# 11-DPLL-2.net
KiCad netlist of a schematic drawn in Altium Designer
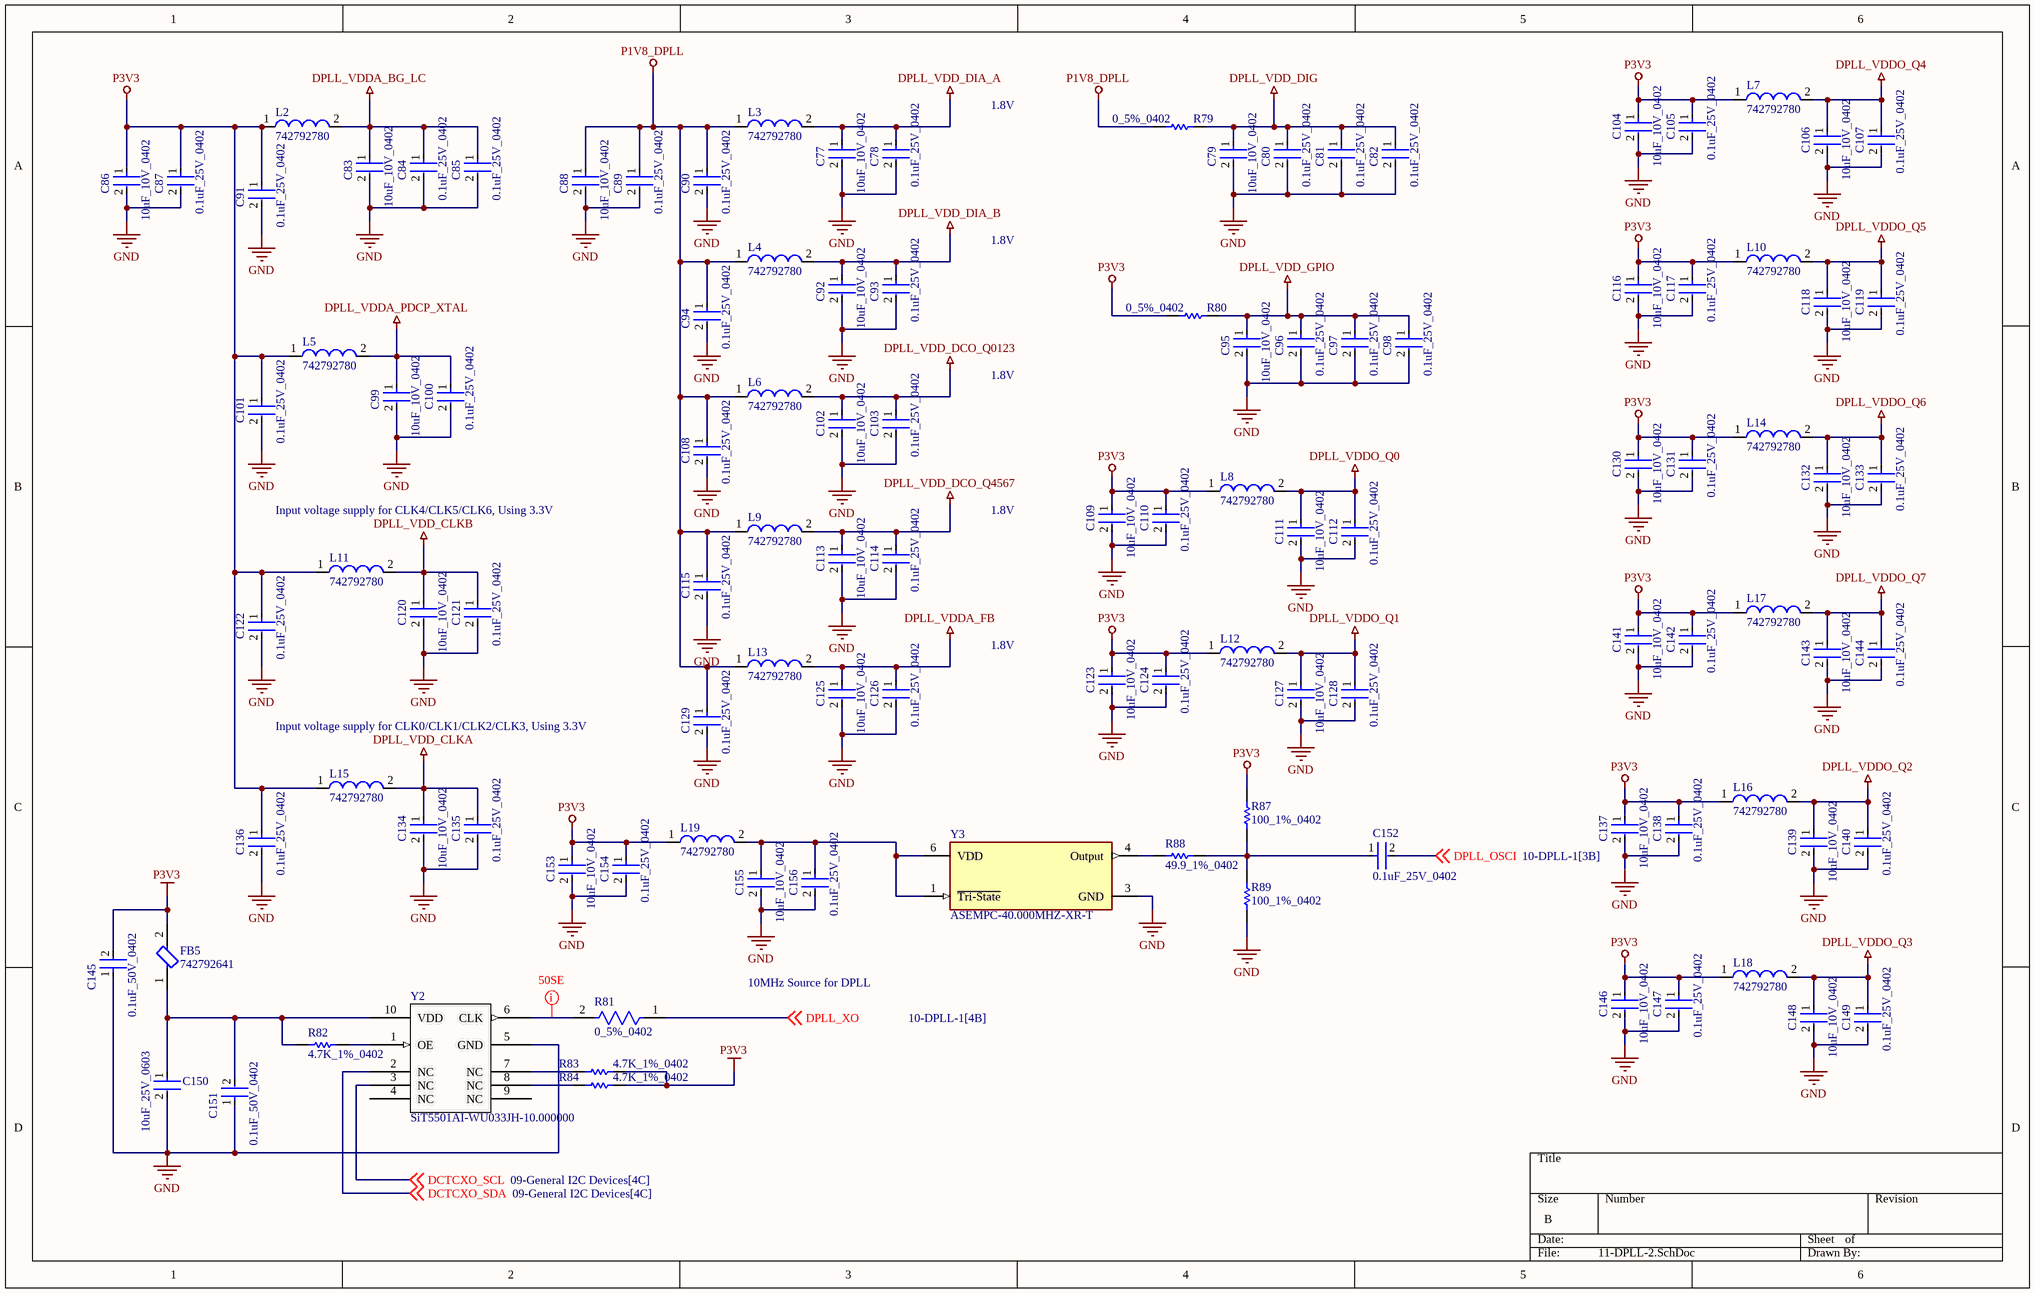
[diagram p0: 11-DPLL-2.SchDoc]

(export (version "E")
  (design (tool "Eeschema 10.0.6"))
  (components
    (comp (ref "C77")
      (value "10uF_10V_0402")
      (footprint "FP-CL05A106MP5NUNC-MFG")
      (description "CAP CER 10UF 10V X5R 0402")
      (fields
        (field (name "OCTOPART") "https://octopart.com/cl05a106mp5nunc-samsung-22457395")
        (field (name "TOLERANCE") "20%")
      )
      (libsource (lib "Altium Content Vault") (part "b4654b650e69147ec39a6b967a45e02"))
    )
    (comp (ref "C78")
      (value "0.1uF_25V_0402")
      (footprint "FP-0402-L_1_0_1-W_0_5_0_1-IPC_C")
      (description "General Purpose Ceramic Capacitor, 0402, 100nF, 10%, X7R, 15%, 25V")
      (fields (field (name "VOLTAGE") "25V") (field (name "TOLERANCE") "10%"))
      (libsource (lib "Altium Content Vault") (part "b4654b650e69147ec39a6b967a45e02"))
    )
    (comp (ref "C79")
      (value "10uF_10V_0402")
      (footprint "FP-CL05A106MP5NUNC-MFG")
      (description "CAP CER 10UF 10V X5R 0402")
      (fields
        (field (name "OCTOPART") "https://octopart.com/cl05a106mp5nunc-samsung-22457395")
        (field (name "TOLERANCE") "20%")
      )
      (libsource (lib "Altium Content Vault") (part "b4654b650e69147ec39a6b967a45e02"))
    )
    (comp (ref "C80")
      (value "0.1uF_25V_0402")
      (footprint "FP-0402-L_1_0_1-W_0_5_0_1-IPC_C")
      (description "General Purpose Ceramic Capacitor, 0402, 100nF, 10%, X7R, 15%, 25V")
      (fields (field (name "VOLTAGE") "25V") (field (name "TOLERANCE") "10%"))
      (libsource (lib "Altium Content Vault") (part "b4654b650e69147ec39a6b967a45e02"))
    )
    (comp (ref "C81")
      (value "0.1uF_25V_0402")
      (footprint "FP-0402-L_1_0_1-W_0_5_0_1-IPC_C")
      (description "General Purpose Ceramic Capacitor, 0402, 100nF, 10%, X7R, 15%, 25V")
      (fields (field (name "VOLTAGE") "25V") (field (name "TOLERANCE") "10%"))
      (libsource (lib "Altium Content Vault") (part "b4654b650e69147ec39a6b967a45e02"))
    )
    (comp (ref "C82")
      (value "0.1uF_25V_0402")
      (footprint "FP-0402-L_1_0_1-W_0_5_0_1-IPC_C")
      (description "General Purpose Ceramic Capacitor, 0402, 100nF, 10%, X7R, 15%, 25V")
      (fields (field (name "VOLTAGE") "25V") (field (name "TOLERANCE") "10%"))
      (libsource (lib "Altium Content Vault") (part "b4654b650e69147ec39a6b967a45e02"))
    )
    (comp (ref "C83")
      (value "10uF_10V_0402")
      (footprint "FP-CL05A106MP5NUNC-MFG")
      (description "CAP CER 10UF 10V X5R 0402")
      (fields
        (field (name "OCTOPART") "https://octopart.com/cl05a106mp5nunc-samsung-22457395")
        (field (name "TOLERANCE") "20%")
      )
      (libsource (lib "Altium Content Vault") (part "b4654b650e69147ec39a6b967a45e02"))
    )
    (comp (ref "C84")
      (value "0.1uF_25V_0402")
      (footprint "FP-0402-L_1_0_1-W_0_5_0_1-IPC_C")
      (description "General Purpose Ceramic Capacitor, 0402, 100nF, 10%, X7R, 15%, 25V")
      (fields (field (name "VOLTAGE") "25V") (field (name "TOLERANCE") "10%"))
      (libsource (lib "Altium Content Vault") (part "b4654b650e69147ec39a6b967a45e02"))
    )
    (comp (ref "C85")
      (value "0.1uF_25V_0402")
      (footprint "FP-0402-L_1_0_1-W_0_5_0_1-IPC_C")
      (description "General Purpose Ceramic Capacitor, 0402, 100nF, 10%, X7R, 15%, 25V")
      (fields (field (name "VOLTAGE") "25V") (field (name "TOLERANCE") "10%"))
      (libsource (lib "Altium Content Vault") (part "b4654b650e69147ec39a6b967a45e02"))
    )
    (comp (ref "C86")
      (value "10uF_10V_0402")
      (footprint "FP-CL05A106MP5NUNC-MFG")
      (description "CAP CER 10UF 10V X5R 0402")
      (fields
        (field (name "OCTOPART") "https://octopart.com/cl05a106mp5nunc-samsung-22457395")
        (field (name "TOLERANCE") "20%")
      )
      (libsource (lib "Altium Content Vault") (part "b4654b650e69147ec39a6b967a45e02"))
    )
    (comp (ref "C87")
      (value "0.1uF_25V_0402")
      (footprint "FP-0402-L_1_0_1-W_0_5_0_1-IPC_C")
      (description "General Purpose Ceramic Capacitor, 0402, 100nF, 10%, X7R, 15%, 25V")
      (fields (field (name "VOLTAGE") "25V") (field (name "TOLERANCE") "10%"))
      (libsource (lib "Altium Content Vault") (part "b4654b650e69147ec39a6b967a45e02"))
    )
    (comp (ref "C88")
      (value "10uF_10V_0402")
      (footprint "FP-CL05A106MP5NUNC-MFG")
      (description "CAP CER 10UF 10V X5R 0402")
      (fields
        (field (name "OCTOPART") "https://octopart.com/cl05a106mp5nunc-samsung-22457395")
        (field (name "TOLERANCE") "20%")
      )
      (libsource (lib "Altium Content Vault") (part "b4654b650e69147ec39a6b967a45e02"))
    )
    (comp (ref "C89")
      (value "0.1uF_25V_0402")
      (footprint "FP-0402-L_1_0_1-W_0_5_0_1-IPC_C")
      (description "General Purpose Ceramic Capacitor, 0402, 100nF, 10%, X7R, 15%, 25V")
      (fields (field (name "VOLTAGE") "25V") (field (name "TOLERANCE") "10%"))
      (libsource (lib "Altium Content Vault") (part "b4654b650e69147ec39a6b967a45e02"))
    )
    (comp (ref "C90")
      (value "0.1uF_25V_0402")
      (footprint "FP-0402-L_1_0_1-W_0_5_0_1-IPC_C")
      (description "General Purpose Ceramic Capacitor, 0402, 100nF, 10%, X7R, 15%, 25V")
      (fields (field (name "VOLTAGE") "25V") (field (name "TOLERANCE") "10%"))
      (libsource (lib "Altium Content Vault") (part "b4654b650e69147ec39a6b967a45e02"))
    )
    (comp (ref "C91")
      (value "0.1uF_25V_0402")
      (footprint "FP-0402-L_1_0_1-W_0_5_0_1-IPC_C")
      (description "General Purpose Ceramic Capacitor, 0402, 100nF, 10%, X7R, 15%, 25V")
      (fields (field (name "VOLTAGE") "25V") (field (name "TOLERANCE") "10%"))
      (libsource (lib "Altium Content Vault") (part "b4654b650e69147ec39a6b967a45e02"))
    )
    (comp (ref "C92")
      (value "10uF_10V_0402")
      (footprint "FP-CL05A106MP5NUNC-MFG")
      (description "CAP CER 10UF 10V X5R 0402")
      (fields
        (field (name "OCTOPART") "https://octopart.com/cl05a106mp5nunc-samsung-22457395")
        (field (name "TOLERANCE") "20%")
      )
      (libsource (lib "Altium Content Vault") (part "b4654b650e69147ec39a6b967a45e02"))
    )
    (comp (ref "C93")
      (value "0.1uF_25V_0402")
      (footprint "FP-0402-L_1_0_1-W_0_5_0_1-IPC_C")
      (description "General Purpose Ceramic Capacitor, 0402, 100nF, 10%, X7R, 15%, 25V")
      (fields (field (name "VOLTAGE") "25V") (field (name "TOLERANCE") "10%"))
      (libsource (lib "Altium Content Vault") (part "b4654b650e69147ec39a6b967a45e02"))
    )
    (comp (ref "C94")
      (value "0.1uF_25V_0402")
      (footprint "FP-0402-L_1_0_1-W_0_5_0_1-IPC_C")
      (description "General Purpose Ceramic Capacitor, 0402, 100nF, 10%, X7R, 15%, 25V")
      (fields (field (name "VOLTAGE") "25V") (field (name "TOLERANCE") "10%"))
      (libsource (lib "Altium Content Vault") (part "b4654b650e69147ec39a6b967a45e02"))
    )
    (comp (ref "C95")
      (value "10uF_10V_0402")
      (footprint "FP-CL05A106MP5NUNC-MFG")
      (description "CAP CER 10UF 10V X5R 0402")
      (fields
        (field (name "OCTOPART") "https://octopart.com/cl05a106mp5nunc-samsung-22457395")
        (field (name "TOLERANCE") "20%")
      )
      (libsource (lib "Altium Content Vault") (part "b4654b650e69147ec39a6b967a45e02"))
    )
    (comp (ref "C96")
      (value "0.1uF_25V_0402")
      (footprint "FP-0402-L_1_0_1-W_0_5_0_1-IPC_C")
      (description "General Purpose Ceramic Capacitor, 0402, 100nF, 10%, X7R, 15%, 25V")
      (fields (field (name "VOLTAGE") "25V") (field (name "TOLERANCE") "10%"))
      (libsource (lib "Altium Content Vault") (part "b4654b650e69147ec39a6b967a45e02"))
    )
    (comp (ref "C97")
      (value "0.1uF_25V_0402")
      (footprint "FP-0402-L_1_0_1-W_0_5_0_1-IPC_C")
      (description "General Purpose Ceramic Capacitor, 0402, 100nF, 10%, X7R, 15%, 25V")
      (fields (field (name "VOLTAGE") "25V") (field (name "TOLERANCE") "10%"))
      (libsource (lib "Altium Content Vault") (part "b4654b650e69147ec39a6b967a45e02"))
    )
    (comp (ref "C98")
      (value "0.1uF_25V_0402")
      (footprint "FP-0402-L_1_0_1-W_0_5_0_1-IPC_C")
      (description "General Purpose Ceramic Capacitor, 0402, 100nF, 10%, X7R, 15%, 25V")
      (fields (field (name "VOLTAGE") "25V") (field (name "TOLERANCE") "10%"))
      (libsource (lib "Altium Content Vault") (part "b4654b650e69147ec39a6b967a45e02"))
    )
    (comp (ref "C99")
      (value "10uF_10V_0402")
      (footprint "FP-CL05A106MP5NUNC-MFG")
      (description "CAP CER 10UF 10V X5R 0402")
      (fields
        (field (name "OCTOPART") "https://octopart.com/cl05a106mp5nunc-samsung-22457395")
        (field (name "TOLERANCE") "20%")
      )
      (libsource (lib "Altium Content Vault") (part "b4654b650e69147ec39a6b967a45e02"))
    )
    (comp (ref "C100")
      (value "0.1uF_25V_0402")
      (footprint "FP-0402-L_1_0_1-W_0_5_0_1-IPC_C")
      (description "General Purpose Ceramic Capacitor, 0402, 100nF, 10%, X7R, 15%, 25V")
      (fields (field (name "VOLTAGE") "25V") (field (name "TOLERANCE") "10%"))
      (libsource (lib "Altium Content Vault") (part "b4654b650e69147ec39a6b967a45e02"))
    )
    (comp (ref "C101")
      (value "0.1uF_25V_0402")
      (footprint "FP-0402-L_1_0_1-W_0_5_0_1-IPC_C")
      (description "General Purpose Ceramic Capacitor, 0402, 100nF, 10%, X7R, 15%, 25V")
      (fields (field (name "VOLTAGE") "25V") (field (name "TOLERANCE") "10%"))
      (libsource (lib "Altium Content Vault") (part "b4654b650e69147ec39a6b967a45e02"))
    )
    (comp (ref "C102")
      (value "10uF_10V_0402")
      (footprint "FP-CL05A106MP5NUNC-MFG")
      (description "CAP CER 10UF 10V X5R 0402")
      (fields
        (field (name "OCTOPART") "https://octopart.com/cl05a106mp5nunc-samsung-22457395")
        (field (name "TOLERANCE") "20%")
      )
      (libsource (lib "Altium Content Vault") (part "b4654b650e69147ec39a6b967a45e02"))
    )
    (comp (ref "C103")
      (value "0.1uF_25V_0402")
      (footprint "FP-0402-L_1_0_1-W_0_5_0_1-IPC_C")
      (description "General Purpose Ceramic Capacitor, 0402, 100nF, 10%, X7R, 15%, 25V")
      (fields (field (name "VOLTAGE") "25V") (field (name "TOLERANCE") "10%"))
      (libsource (lib "Altium Content Vault") (part "b4654b650e69147ec39a6b967a45e02"))
    )
    (comp (ref "C104")
      (value "10uF_10V_0402")
      (footprint "FP-CL05A106MP5NUNC-MFG")
      (description "CAP CER 10UF 10V X5R 0402")
      (fields
        (field (name "OCTOPART") "https://octopart.com/cl05a106mp5nunc-samsung-22457395")
        (field (name "TOLERANCE") "20%")
      )
      (libsource (lib "Altium Content Vault") (part "b4654b650e69147ec39a6b967a45e02"))
    )
    (comp (ref "C105")
      (value "0.1uF_25V_0402")
      (footprint "FP-0402-L_1_0_1-W_0_5_0_1-IPC_C")
      (description "General Purpose Ceramic Capacitor, 0402, 100nF, 10%, X7R, 15%, 25V")
      (fields (field (name "VOLTAGE") "25V") (field (name "TOLERANCE") "10%"))
      (libsource (lib "Altium Content Vault") (part "b4654b650e69147ec39a6b967a45e02"))
    )
    (comp (ref "C106")
      (value "10uF_10V_0402")
      (footprint "FP-CL05A106MP5NUNC-MFG")
      (description "CAP CER 10UF 10V X5R 0402")
      (fields
        (field (name "OCTOPART") "https://octopart.com/cl05a106mp5nunc-samsung-22457395")
        (field (name "TOLERANCE") "20%")
      )
      (libsource (lib "Altium Content Vault") (part "b4654b650e69147ec39a6b967a45e02"))
    )
    (comp (ref "C107")
      (value "0.1uF_25V_0402")
      (footprint "FP-0402-L_1_0_1-W_0_5_0_1-IPC_C")
      (description "General Purpose Ceramic Capacitor, 0402, 100nF, 10%, X7R, 15%, 25V")
      (fields (field (name "VOLTAGE") "25V") (field (name "TOLERANCE") "10%"))
      (libsource (lib "Altium Content Vault") (part "b4654b650e69147ec39a6b967a45e02"))
    )
    (comp (ref "C108")
      (value "0.1uF_25V_0402")
      (footprint "FP-0402-L_1_0_1-W_0_5_0_1-IPC_C")
      (description "General Purpose Ceramic Capacitor, 0402, 100nF, 10%, X7R, 15%, 25V")
      (fields (field (name "VOLTAGE") "25V") (field (name "TOLERANCE") "10%"))
      (libsource (lib "Altium Content Vault") (part "b4654b650e69147ec39a6b967a45e02"))
    )
    (comp (ref "C109")
      (value "10uF_10V_0402")
      (footprint "FP-CL05A106MP5NUNC-MFG")
      (description "CAP CER 10UF 10V X5R 0402")
      (fields
        (field (name "OCTOPART") "https://octopart.com/cl05a106mp5nunc-samsung-22457395")
        (field (name "TOLERANCE") "20%")
      )
      (libsource (lib "Altium Content Vault") (part "b4654b650e69147ec39a6b967a45e02"))
    )
    (comp (ref "C110")
      (value "0.1uF_25V_0402")
      (footprint "FP-0402-L_1_0_1-W_0_5_0_1-IPC_C")
      (description "General Purpose Ceramic Capacitor, 0402, 100nF, 10%, X7R, 15%, 25V")
      (fields (field (name "VOLTAGE") "25V") (field (name "TOLERANCE") "10%"))
      (libsource (lib "Altium Content Vault") (part "b4654b650e69147ec39a6b967a45e02"))
    )
    (comp (ref "C111")
      (value "10uF_10V_0402")
      (footprint "FP-CL05A106MP5NUNC-MFG")
      (description "CAP CER 10UF 10V X5R 0402")
      (fields
        (field (name "OCTOPART") "https://octopart.com/cl05a106mp5nunc-samsung-22457395")
        (field (name "TOLERANCE") "20%")
      )
      (libsource (lib "Altium Content Vault") (part "b4654b650e69147ec39a6b967a45e02"))
    )
    (comp (ref "C112")
      (value "0.1uF_25V_0402")
      (footprint "FP-0402-L_1_0_1-W_0_5_0_1-IPC_C")
      (description "General Purpose Ceramic Capacitor, 0402, 100nF, 10%, X7R, 15%, 25V")
      (fields (field (name "VOLTAGE") "25V") (field (name "TOLERANCE") "10%"))
      (libsource (lib "Altium Content Vault") (part "b4654b650e69147ec39a6b967a45e02"))
    )
    (comp (ref "C113")
      (value "10uF_10V_0402")
      (footprint "FP-CL05A106MP5NUNC-MFG")
      (description "CAP CER 10UF 10V X5R 0402")
      (fields
        (field (name "OCTOPART") "https://octopart.com/cl05a106mp5nunc-samsung-22457395")
        (field (name "TOLERANCE") "20%")
      )
      (libsource (lib "Altium Content Vault") (part "b4654b650e69147ec39a6b967a45e02"))
    )
    (comp (ref "C114")
      (value "0.1uF_25V_0402")
      (footprint "FP-0402-L_1_0_1-W_0_5_0_1-IPC_C")
      (description "General Purpose Ceramic Capacitor, 0402, 100nF, 10%, X7R, 15%, 25V")
      (fields (field (name "VOLTAGE") "25V") (field (name "TOLERANCE") "10%"))
      (libsource (lib "Altium Content Vault") (part "b4654b650e69147ec39a6b967a45e02"))
    )
    (comp (ref "C115")
      (value "0.1uF_25V_0402")
      (footprint "FP-0402-L_1_0_1-W_0_5_0_1-IPC_C")
      (description "General Purpose Ceramic Capacitor, 0402, 100nF, 10%, X7R, 15%, 25V")
      (fields (field (name "VOLTAGE") "25V") (field (name "TOLERANCE") "10%"))
      (libsource (lib "Altium Content Vault") (part "b4654b650e69147ec39a6b967a45e02"))
    )
    (comp (ref "C116")
      (value "10uF_10V_0402")
      (footprint "FP-CL05A106MP5NUNC-MFG")
      (description "CAP CER 10UF 10V X5R 0402")
      (fields
        (field (name "OCTOPART") "https://octopart.com/cl05a106mp5nunc-samsung-22457395")
        (field (name "TOLERANCE") "20%")
      )
      (libsource (lib "Altium Content Vault") (part "b4654b650e69147ec39a6b967a45e02"))
    )
    (comp (ref "C117")
      (value "0.1uF_25V_0402")
      (footprint "FP-0402-L_1_0_1-W_0_5_0_1-IPC_C")
      (description "General Purpose Ceramic Capacitor, 0402, 100nF, 10%, X7R, 15%, 25V")
      (fields (field (name "VOLTAGE") "25V") (field (name "TOLERANCE") "10%"))
      (libsource (lib "Altium Content Vault") (part "b4654b650e69147ec39a6b967a45e02"))
    )
    (comp (ref "C118")
      (value "10uF_10V_0402")
      (footprint "FP-CL05A106MP5NUNC-MFG")
      (description "CAP CER 10UF 10V X5R 0402")
      (fields
        (field (name "OCTOPART") "https://octopart.com/cl05a106mp5nunc-samsung-22457395")
        (field (name "TOLERANCE") "20%")
      )
      (libsource (lib "Altium Content Vault") (part "b4654b650e69147ec39a6b967a45e02"))
    )
    (comp (ref "C119")
      (value "0.1uF_25V_0402")
      (footprint "FP-0402-L_1_0_1-W_0_5_0_1-IPC_C")
      (description "General Purpose Ceramic Capacitor, 0402, 100nF, 10%, X7R, 15%, 25V")
      (fields (field (name "VOLTAGE") "25V") (field (name "TOLERANCE") "10%"))
      (libsource (lib "Altium Content Vault") (part "b4654b650e69147ec39a6b967a45e02"))
    )
    (comp (ref "C120")
      (value "10uF_10V_0402")
      (footprint "FP-CL05A106MP5NUNC-MFG")
      (description "CAP CER 10UF 10V X5R 0402")
      (fields
        (field (name "OCTOPART") "https://octopart.com/cl05a106mp5nunc-samsung-22457395")
        (field (name "TOLERANCE") "20%")
      )
      (libsource (lib "Altium Content Vault") (part "b4654b650e69147ec39a6b967a45e02"))
    )
    (comp (ref "C121")
      (value "0.1uF_25V_0402")
      (footprint "FP-0402-L_1_0_1-W_0_5_0_1-IPC_C")
      (description "General Purpose Ceramic Capacitor, 0402, 100nF, 10%, X7R, 15%, 25V")
      (fields (field (name "VOLTAGE") "25V") (field (name "TOLERANCE") "10%"))
      (libsource (lib "Altium Content Vault") (part "b4654b650e69147ec39a6b967a45e02"))
    )
    (comp (ref "C122")
      (value "0.1uF_25V_0402")
      (footprint "FP-0402-L_1_0_1-W_0_5_0_1-IPC_C")
      (description "General Purpose Ceramic Capacitor, 0402, 100nF, 10%, X7R, 15%, 25V")
      (fields (field (name "VOLTAGE") "25V") (field (name "TOLERANCE") "10%"))
      (libsource (lib "Altium Content Vault") (part "b4654b650e69147ec39a6b967a45e02"))
    )
    (comp (ref "C123")
      (value "10uF_10V_0402")
      (footprint "FP-CL05A106MP5NUNC-MFG")
      (description "CAP CER 10UF 10V X5R 0402")
      (fields
        (field (name "OCTOPART") "https://octopart.com/cl05a106mp5nunc-samsung-22457395")
        (field (name "TOLERANCE") "20%")
      )
      (libsource (lib "Altium Content Vault") (part "b4654b650e69147ec39a6b967a45e02"))
    )
    (comp (ref "C124")
      (value "0.1uF_25V_0402")
      (footprint "FP-0402-L_1_0_1-W_0_5_0_1-IPC_C")
      (description "General Purpose Ceramic Capacitor, 0402, 100nF, 10%, X7R, 15%, 25V")
      (fields (field (name "VOLTAGE") "25V") (field (name "TOLERANCE") "10%"))
      (libsource (lib "Altium Content Vault") (part "b4654b650e69147ec39a6b967a45e02"))
    )
    (comp (ref "C125")
      (value "10uF_10V_0402")
      (footprint "FP-CL05A106MP5NUNC-MFG")
      (description "CAP CER 10UF 10V X5R 0402")
      (fields
        (field (name "OCTOPART") "https://octopart.com/cl05a106mp5nunc-samsung-22457395")
        (field (name "TOLERANCE") "20%")
      )
      (libsource (lib "Altium Content Vault") (part "b4654b650e69147ec39a6b967a45e02"))
    )
    (comp (ref "C126")
      (value "0.1uF_25V_0402")
      (footprint "FP-0402-L_1_0_1-W_0_5_0_1-IPC_C")
      (description "General Purpose Ceramic Capacitor, 0402, 100nF, 10%, X7R, 15%, 25V")
      (fields (field (name "VOLTAGE") "25V") (field (name "TOLERANCE") "10%"))
      (libsource (lib "Altium Content Vault") (part "b4654b650e69147ec39a6b967a45e02"))
    )
    (comp (ref "C127")
      (value "10uF_10V_0402")
      (footprint "FP-CL05A106MP5NUNC-MFG")
      (description "CAP CER 10UF 10V X5R 0402")
      (fields
        (field (name "OCTOPART") "https://octopart.com/cl05a106mp5nunc-samsung-22457395")
        (field (name "TOLERANCE") "20%")
      )
      (libsource (lib "Altium Content Vault") (part "b4654b650e69147ec39a6b967a45e02"))
    )
    (comp (ref "C128")
      (value "0.1uF_25V_0402")
      (footprint "FP-0402-L_1_0_1-W_0_5_0_1-IPC_C")
      (description "General Purpose Ceramic Capacitor, 0402, 100nF, 10%, X7R, 15%, 25V")
      (fields (field (name "VOLTAGE") "25V") (field (name "TOLERANCE") "10%"))
      (libsource (lib "Altium Content Vault") (part "b4654b650e69147ec39a6b967a45e02"))
    )
    (comp (ref "C129")
      (value "0.1uF_25V_0402")
      (footprint "FP-0402-L_1_0_1-W_0_5_0_1-IPC_C")
      (description "General Purpose Ceramic Capacitor, 0402, 100nF, 10%, X7R, 15%, 25V")
      (fields (field (name "VOLTAGE") "25V") (field (name "TOLERANCE") "10%"))
      (libsource (lib "Altium Content Vault") (part "b4654b650e69147ec39a6b967a45e02"))
    )
    (comp (ref "C130")
      (value "10uF_10V_0402")
      (footprint "FP-CL05A106MP5NUNC-MFG")
      (description "CAP CER 10UF 10V X5R 0402")
      (fields
        (field (name "OCTOPART") "https://octopart.com/cl05a106mp5nunc-samsung-22457395")
        (field (name "TOLERANCE") "20%")
      )
      (libsource (lib "Altium Content Vault") (part "b4654b650e69147ec39a6b967a45e02"))
    )
    (comp (ref "C131")
      (value "0.1uF_25V_0402")
      (footprint "FP-0402-L_1_0_1-W_0_5_0_1-IPC_C")
      (description "General Purpose Ceramic Capacitor, 0402, 100nF, 10%, X7R, 15%, 25V")
      (fields (field (name "VOLTAGE") "25V") (field (name "TOLERANCE") "10%"))
      (libsource (lib "Altium Content Vault") (part "b4654b650e69147ec39a6b967a45e02"))
    )
    (comp (ref "C132")
      (value "10uF_10V_0402")
      (footprint "FP-CL05A106MP5NUNC-MFG")
      (description "CAP CER 10UF 10V X5R 0402")
      (fields
        (field (name "OCTOPART") "https://octopart.com/cl05a106mp5nunc-samsung-22457395")
        (field (name "TOLERANCE") "20%")
      )
      (libsource (lib "Altium Content Vault") (part "b4654b650e69147ec39a6b967a45e02"))
    )
    (comp (ref "C133")
      (value "0.1uF_25V_0402")
      (footprint "FP-0402-L_1_0_1-W_0_5_0_1-IPC_C")
      (description "General Purpose Ceramic Capacitor, 0402, 100nF, 10%, X7R, 15%, 25V")
      (fields (field (name "VOLTAGE") "25V") (field (name "TOLERANCE") "10%"))
      (libsource (lib "Altium Content Vault") (part "b4654b650e69147ec39a6b967a45e02"))
    )
    (comp (ref "C134")
      (value "10uF_10V_0402")
      (footprint "FP-CL05A106MP5NUNC-MFG")
      (description "CAP CER 10UF 10V X5R 0402")
      (fields
        (field (name "OCTOPART") "https://octopart.com/cl05a106mp5nunc-samsung-22457395")
        (field (name "TOLERANCE") "20%")
      )
      (libsource (lib "Altium Content Vault") (part "b4654b650e69147ec39a6b967a45e02"))
    )
    (comp (ref "C135")
      (value "0.1uF_25V_0402")
      (footprint "FP-0402-L_1_0_1-W_0_5_0_1-IPC_C")
      (description "General Purpose Ceramic Capacitor, 0402, 100nF, 10%, X7R, 15%, 25V")
      (fields (field (name "VOLTAGE") "25V") (field (name "TOLERANCE") "10%"))
      (libsource (lib "Altium Content Vault") (part "b4654b650e69147ec39a6b967a45e02"))
    )
    (comp (ref "C136")
      (value "0.1uF_25V_0402")
      (footprint "FP-0402-L_1_0_1-W_0_5_0_1-IPC_C")
      (description "General Purpose Ceramic Capacitor, 0402, 100nF, 10%, X7R, 15%, 25V")
      (fields (field (name "VOLTAGE") "25V") (field (name "TOLERANCE") "10%"))
      (libsource (lib "Altium Content Vault") (part "b4654b650e69147ec39a6b967a45e02"))
    )
    (comp (ref "C137")
      (value "10uF_10V_0402")
      (footprint "FP-CL05A106MP5NUNC-MFG")
      (description "CAP CER 10UF 10V X5R 0402")
      (fields
        (field (name "OCTOPART") "https://octopart.com/cl05a106mp5nunc-samsung-22457395")
        (field (name "TOLERANCE") "20%")
      )
      (libsource (lib "Altium Content Vault") (part "b4654b650e69147ec39a6b967a45e02"))
    )
    (comp (ref "C138")
      (value "0.1uF_25V_0402")
      (footprint "FP-0402-L_1_0_1-W_0_5_0_1-IPC_C")
      (description "General Purpose Ceramic Capacitor, 0402, 100nF, 10%, X7R, 15%, 25V")
      (fields (field (name "VOLTAGE") "25V") (field (name "TOLERANCE") "10%"))
      (libsource (lib "Altium Content Vault") (part "b4654b650e69147ec39a6b967a45e02"))
    )
    (comp (ref "C139")
      (value "10uF_10V_0402")
      (footprint "FP-CL05A106MP5NUNC-MFG")
      (description "CAP CER 10UF 10V X5R 0402")
      (fields
        (field (name "OCTOPART") "https://octopart.com/cl05a106mp5nunc-samsung-22457395")
        (field (name "TOLERANCE") "20%")
      )
      (libsource (lib "Altium Content Vault") (part "b4654b650e69147ec39a6b967a45e02"))
    )
    (comp (ref "C140")
      (value "0.1uF_25V_0402")
      (footprint "FP-0402-L_1_0_1-W_0_5_0_1-IPC_C")
      (description "General Purpose Ceramic Capacitor, 0402, 100nF, 10%, X7R, 15%, 25V")
      (fields (field (name "VOLTAGE") "25V") (field (name "TOLERANCE") "10%"))
      (libsource (lib "Altium Content Vault") (part "b4654b650e69147ec39a6b967a45e02"))
    )
    (comp (ref "C141")
      (value "10uF_10V_0402")
      (footprint "FP-CL05A106MP5NUNC-MFG")
      (description "CAP CER 10UF 10V X5R 0402")
      (fields
        (field (name "OCTOPART") "https://octopart.com/cl05a106mp5nunc-samsung-22457395")
        (field (name "TOLERANCE") "20%")
      )
      (libsource (lib "Altium Content Vault") (part "b4654b650e69147ec39a6b967a45e02"))
    )
    (comp (ref "C142")
      (value "0.1uF_25V_0402")
      (footprint "FP-0402-L_1_0_1-W_0_5_0_1-IPC_C")
      (description "General Purpose Ceramic Capacitor, 0402, 100nF, 10%, X7R, 15%, 25V")
      (fields (field (name "VOLTAGE") "25V") (field (name "TOLERANCE") "10%"))
      (libsource (lib "Altium Content Vault") (part "b4654b650e69147ec39a6b967a45e02"))
    )
    (comp (ref "C143")
      (value "10uF_10V_0402")
      (footprint "FP-CL05A106MP5NUNC-MFG")
      (description "CAP CER 10UF 10V X5R 0402")
      (fields
        (field (name "OCTOPART") "https://octopart.com/cl05a106mp5nunc-samsung-22457395")
        (field (name "TOLERANCE") "20%")
      )
      (libsource (lib "Altium Content Vault") (part "b4654b650e69147ec39a6b967a45e02"))
    )
    (comp (ref "C144")
      (value "0.1uF_25V_0402")
      (footprint "FP-0402-L_1_0_1-W_0_5_0_1-IPC_C")
      (description "General Purpose Ceramic Capacitor, 0402, 100nF, 10%, X7R, 15%, 25V")
      (fields (field (name "VOLTAGE") "25V") (field (name "TOLERANCE") "10%"))
      (libsource (lib "Altium Content Vault") (part "b4654b650e69147ec39a6b967a45e02"))
    )
    (comp (ref "C145")
      (value "0.1uF_50V_0402")
      (footprint "FP-C1005-050-0_05-IPC_C")
      (description "Multilayer Ceramic Capacitors 100nF ±10% 50V X7R SMD 0402")
      (fields (field (name "VOLTAGE") "50V") (field (name "TOLERANCE") "10%"))
      (libsource (lib "Altium Content Vault") (part "b4654b650e69147ec39a6b967a45e02"))
    )
    (comp (ref "C146")
      (value "10uF_10V_0402")
      (footprint "FP-CL05A106MP5NUNC-MFG")
      (description "CAP CER 10UF 10V X5R 0402")
      (fields
        (field (name "OCTOPART") "https://octopart.com/cl05a106mp5nunc-samsung-22457395")
        (field (name "TOLERANCE") "20%")
      )
      (libsource (lib "Altium Content Vault") (part "b4654b650e69147ec39a6b967a45e02"))
    )
    (comp (ref "C147")
      (value "0.1uF_25V_0402")
      (footprint "FP-0402-L_1_0_1-W_0_5_0_1-IPC_C")
      (description "General Purpose Ceramic Capacitor, 0402, 100nF, 10%, X7R, 15%, 25V")
      (fields (field (name "VOLTAGE") "25V") (field (name "TOLERANCE") "10%"))
      (libsource (lib "Altium Content Vault") (part "b4654b650e69147ec39a6b967a45e02"))
    )
    (comp (ref "C148")
      (value "10uF_10V_0402")
      (footprint "FP-CL05A106MP5NUNC-MFG")
      (description "CAP CER 10UF 10V X5R 0402")
      (fields
        (field (name "OCTOPART") "https://octopart.com/cl05a106mp5nunc-samsung-22457395")
        (field (name "TOLERANCE") "20%")
      )
      (libsource (lib "Altium Content Vault") (part "b4654b650e69147ec39a6b967a45e02"))
    )
    (comp (ref "C149")
      (value "0.1uF_25V_0402")
      (footprint "FP-0402-L_1_0_1-W_0_5_0_1-IPC_C")
      (description "General Purpose Ceramic Capacitor, 0402, 100nF, 10%, X7R, 15%, 25V")
      (fields (field (name "VOLTAGE") "25V") (field (name "TOLERANCE") "10%"))
      (libsource (lib "Altium Content Vault") (part "b4654b650e69147ec39a6b967a45e02"))
    )
    (comp (ref "C150")
      (value "10uF_25V_0603")
      (footprint "FP-CL10-IPC_C")
      (description "Cap Ceramic 10uF 25V X5R ±20% Pad SMD 0603 +85°C T/R")
      (fields (field (name "TOLERANCE") "20%"))
      (libsource (lib "Altium Content Vault") (part "b4654b650e69147ec39a6b967a45e02"))
    )
    (comp (ref "C151")
      (value "0.1uF_50V_0402")
      (footprint "FP-C1005-050-0_05-IPC_C")
      (description "Multilayer Ceramic Capacitors 100nF ±10% 50V X7R SMD 0402")
      (fields (field (name "VOLTAGE") "50V") (field (name "TOLERANCE") "10%"))
      (libsource (lib "Altium Content Vault") (part "b4654b650e69147ec39a6b967a45e02"))
    )
    (comp (ref "C152")
      (value "0.1uF_25V_0402")
      (footprint "FP-0402-L_1_0_1-W_0_5_0_1-IPC_C")
      (description "General Purpose Ceramic Capacitor, 0402, 100nF, 10%, X7R, 15%, 25V")
      (fields (field (name "VOLTAGE") "25V") (field (name "TOLERANCE") "10%"))
      (libsource (lib "Altium Content Vault") (part "b4654b650e69147ec39a6b967a45e02"))
    )
    (comp (ref "C153")
      (value "10uF_10V_0402")
      (footprint "FP-CL05A106MP5NUNC-MFG")
      (description "CAP CER 10UF 10V X5R 0402")
      (fields
        (field (name "OCTOPART") "https://octopart.com/cl05a106mp5nunc-samsung-22457395")
        (field (name "TOLERANCE") "20%")
      )
      (libsource (lib "Altium Content Vault") (part "b4654b650e69147ec39a6b967a45e02"))
    )
    (comp (ref "C154")
      (value "0.1uF_25V_0402")
      (footprint "FP-0402-L_1_0_1-W_0_5_0_1-IPC_C")
      (description "General Purpose Ceramic Capacitor, 0402, 100nF, 10%, X7R, 15%, 25V")
      (fields (field (name "VOLTAGE") "25V") (field (name "TOLERANCE") "10%"))
      (libsource (lib "Altium Content Vault") (part "b4654b650e69147ec39a6b967a45e02"))
    )
    (comp (ref "C155")
      (value "10uF_10V_0402")
      (footprint "FP-CL05A106MP5NUNC-MFG")
      (description "CAP CER 10UF 10V X5R 0402")
      (fields
        (field (name "OCTOPART") "https://octopart.com/cl05a106mp5nunc-samsung-22457395")
        (field (name "TOLERANCE") "20%")
      )
      (libsource (lib "Altium Content Vault") (part "b4654b650e69147ec39a6b967a45e02"))
    )
    (comp (ref "C156")
      (value "0.1uF_25V_0402")
      (footprint "FP-0402-L_1_0_1-W_0_5_0_1-IPC_C")
      (description "General Purpose Ceramic Capacitor, 0402, 100nF, 10%, X7R, 15%, 25V")
      (fields (field (name "VOLTAGE") "25V") (field (name "TOLERANCE") "10%"))
      (libsource (lib "Altium Content Vault") (part "b4654b650e69147ec39a6b967a45e02"))
    )
    (comp (ref "FB5")
      (value "742792641")
      (footprint "FP-742792641-MFG")
      (description "FERRITE BEAD 300 OHM 0603 1LN")
      (fields (field (name "TOLERANCE") "25%"))
      (libsource (lib "Altium Content Vault") (part "5f30dd21d616792df468990f7003faa"))
    )
    (comp (ref "L2")
      (value "742792780")
      (footprint "SMD-0402")
      (description "SMD EMI Suppression Ferrite Bead WE-CBF, Z = 220 Ohm")
      (libsource (lib "Altium Content Vault") (part "PAS-IND-INDUCTOR-2"))
    )
    (comp (ref "L3")
      (value "742792780")
      (footprint "SMD-0402")
      (description "SMD EMI Suppression Ferrite Bead WE-CBF, Z = 220 Ohm")
      (libsource (lib "Altium Content Vault") (part "PAS-IND-INDUCTOR-2"))
    )
    (comp (ref "L4")
      (value "742792780")
      (footprint "SMD-0402")
      (description "SMD EMI Suppression Ferrite Bead WE-CBF, Z = 220 Ohm")
      (libsource (lib "Altium Content Vault") (part "PAS-IND-INDUCTOR-2"))
    )
    (comp (ref "L5")
      (value "742792780")
      (footprint "SMD-0402")
      (description "SMD EMI Suppression Ferrite Bead WE-CBF, Z = 220 Ohm")
      (libsource (lib "Altium Content Vault") (part "PAS-IND-INDUCTOR-2"))
    )
    (comp (ref "L6")
      (value "742792780")
      (footprint "SMD-0402")
      (description "SMD EMI Suppression Ferrite Bead WE-CBF, Z = 220 Ohm")
      (libsource (lib "Altium Content Vault") (part "PAS-IND-INDUCTOR-2"))
    )
    (comp (ref "L7")
      (value "742792780")
      (footprint "SMD-0402")
      (description "SMD EMI Suppression Ferrite Bead WE-CBF, Z = 220 Ohm")
      (libsource (lib "Altium Content Vault") (part "PAS-IND-INDUCTOR-2"))
    )
    (comp (ref "L8")
      (value "742792780")
      (footprint "SMD-0402")
      (description "SMD EMI Suppression Ferrite Bead WE-CBF, Z = 220 Ohm")
      (libsource (lib "Altium Content Vault") (part "PAS-IND-INDUCTOR-2"))
    )
    (comp (ref "L9")
      (value "742792780")
      (footprint "SMD-0402")
      (description "SMD EMI Suppression Ferrite Bead WE-CBF, Z = 220 Ohm")
      (libsource (lib "Altium Content Vault") (part "PAS-IND-INDUCTOR-2"))
    )
    (comp (ref "L10")
      (value "742792780")
      (footprint "SMD-0402")
      (description "SMD EMI Suppression Ferrite Bead WE-CBF, Z = 220 Ohm")
      (libsource (lib "Altium Content Vault") (part "PAS-IND-INDUCTOR-2"))
    )
    (comp (ref "L11")
      (value "742792780")
      (footprint "SMD-0402")
      (description "SMD EMI Suppression Ferrite Bead WE-CBF, Z = 220 Ohm")
      (libsource (lib "Altium Content Vault") (part "PAS-IND-INDUCTOR-2"))
    )
    (comp (ref "L12")
      (value "742792780")
      (footprint "SMD-0402")
      (description "SMD EMI Suppression Ferrite Bead WE-CBF, Z = 220 Ohm")
      (libsource (lib "Altium Content Vault") (part "PAS-IND-INDUCTOR-2"))
    )
    (comp (ref "L13")
      (value "742792780")
      (footprint "SMD-0402")
      (description "SMD EMI Suppression Ferrite Bead WE-CBF, Z = 220 Ohm")
      (libsource (lib "Altium Content Vault") (part "PAS-IND-INDUCTOR-2"))
    )
    (comp (ref "L14")
      (value "742792780")
      (footprint "SMD-0402")
      (description "SMD EMI Suppression Ferrite Bead WE-CBF, Z = 220 Ohm")
      (libsource (lib "Altium Content Vault") (part "PAS-IND-INDUCTOR-2"))
    )
    (comp (ref "L15")
      (value "742792780")
      (footprint "SMD-0402")
      (description "SMD EMI Suppression Ferrite Bead WE-CBF, Z = 220 Ohm")
      (libsource (lib "Altium Content Vault") (part "PAS-IND-INDUCTOR-2"))
    )
    (comp (ref "L16")
      (value "742792780")
      (footprint "SMD-0402")
      (description "SMD EMI Suppression Ferrite Bead WE-CBF, Z = 220 Ohm")
      (libsource (lib "Altium Content Vault") (part "PAS-IND-INDUCTOR-2"))
    )
    (comp (ref "L17")
      (value "742792780")
      (footprint "SMD-0402")
      (description "SMD EMI Suppression Ferrite Bead WE-CBF, Z = 220 Ohm")
      (libsource (lib "Altium Content Vault") (part "PAS-IND-INDUCTOR-2"))
    )
    (comp (ref "L18")
      (value "742792780")
      (footprint "SMD-0402")
      (description "SMD EMI Suppression Ferrite Bead WE-CBF, Z = 220 Ohm")
      (libsource (lib "Altium Content Vault") (part "PAS-IND-INDUCTOR-2"))
    )
    (comp (ref "L19")
      (value "742792780")
      (footprint "SMD-0402")
      (description "SMD EMI Suppression Ferrite Bead WE-CBF, Z = 220 Ohm")
      (libsource (lib "Altium Content Vault") (part "PAS-IND-INDUCTOR-2"))
    )
    (comp (ref "R79")
      (value "0_5%_0402")
      (footprint "RESC1005X40X25LL10T10")
      (fields (field (name "MANUFACTURER") "KOA Speer") (field (name "PART NUMBER") "RK73Z1ETTP"))
      (libsource (lib "Altium Content Vault") (part "RES"))
    )
    (comp (ref "R80")
      (value "0_5%_0402")
      (footprint "RESC1005X40X25LL10T10")
      (fields (field (name "MANUFACTURER") "KOA Speer") (field (name "PART NUMBER") "RK73Z1ETTP"))
      (libsource (lib "Altium Content Vault") (part "RES"))
    )
    (comp (ref "R81")
      (value "0_5%_0402")
      (footprint "FP-AC0402-0_37-IPC_B")
      (description "RESISTOR 0402 JUMPER ZERO OHM")
      (fields (field (name "TOLERANCE") "1%"))
      (libsource (lib "Altium Content Vault") (part "1029c3af85768c4190bb7ad29bc67b5"))
    )
    (comp (ref "R82")
      (value "4.7K_1%_0402")
      (footprint "RESC1005X40X25NL10T10")
      (fields (field (name "MANUFACTURER") "Bourns") (field (name "PART NUMBER") "CR0402-FX-4701GLF"))
      (libsource (lib "Altium Content Vault") (part "RES"))
    )
    (comp (ref "R83")
      (value "4.7K_1%_0402")
      (footprint "RESC1005X40X25NL10T10")
      (fields (field (name "MANUFACTURER") "Bourns") (field (name "PART NUMBER") "CR0402-FX-4701GLF"))
      (libsource (lib "Altium Content Vault") (part "RES"))
    )
    (comp (ref "R84")
      (value "4.7K_1%_0402")
      (footprint "RESC1005X40X25NL10T10")
      (fields (field (name "MANUFACTURER") "Bourns") (field (name "PART NUMBER") "CR0402-FX-4701GLF"))
      (libsource (lib "Altium Content Vault") (part "RES"))
    )
    (comp (ref "R87")
      (value "100_1%_0402")
      (footprint "RESC1005X40X25ML05T10")
      (fields (field (name "PART NUMBER") "ERJ-U02F1000X") (field (name "MANUFACTURER") "Panasonic"))
      (libsource (lib "Altium Content Vault") (part "RES"))
    )
    (comp (ref "R88")
      (value "49.9_1%_0402")
      (footprint "RESC1005X40X25NL10T10")
      (fields (field (name "PART NUMBER") "RK73H1ETTP49R9F") (field (name "MANUFACTURER") "KOA Speer"))
      (libsource (lib "Altium Content Vault") (part "RES"))
    )
    (comp (ref "R89")
      (value "100_1%_0402")
      (footprint "RESC1005X40X25ML05T10")
      (fields (field (name "PART NUMBER") "ERJ-U02F1000X") (field (name "MANUFACTURER") "Panasonic"))
      (libsource (lib "Altium Content Vault") (part "RES"))
    )
    (comp (ref "Y2")
      (value "SiTime_SiT5501AC-WU-33E0-10T")
      (footprint "SITIME_SPL-086-CQFN-010-C07050_REV_DRAFT")
      (description "OSC, MEMS, STRATUM 3E, 10.000MHZ, 10PPB STAB, LVCMOS, 3.3V, O/P EN, 7.0X5.0X2.2MM, CQFN-10")
      (fields
        (field (name "MANUFACTURER PART NUMBER") "SiT5501AI-WU033JH-10.000000")
        (field (name "MANUFACTURER") "SiTime")
      )
      (libsource (lib "OCXO_DaughterCard") (part "CMP-OSC-00029-2"))
    )
    (comp (ref "Y3")
      (value "ASEMPC-40.000MHZ-XR-T")
      (footprint "FP-ASEMP-CMOS-MFG")
      (description "MEMS Oscillator 40MHz ±25ppm CMOS 2.25V~3.6V 6-SMD 3.2mm x 2.5mm")
      (libsource (lib "Altium Content Vault") (part "9526c112e3a98a1af86e8f4e974a861"))
    )
  )
  (nets
    (net (code "1") (name "DCTCXO_SCL") (class "Default")
      (node (ref "Y2") (pin "3") (pinfunction "NC_3") (pintype "passive"))
    )
    (net (code "2") (name "DCTCXO_SDA") (class "Default")
      (node (ref "Y2") (pin "2") (pinfunction "NC_2") (pintype "passive"))
    )
    (net (code "3") (name "DPLL_OSCI") (class "Default")
      (node (ref "C152") (pin "2") (pinfunction "2_2") (pintype "passive"))
    )
    (net (code "4") (name "DPLL_VDDA_BG_LC") (class "Default")
      (node (ref "C83") (pin "1") (pinfunction "1_1") (pintype "passive"))
      (node (ref "C84") (pin "1") (pinfunction "1_1") (pintype "passive"))
      (node (ref "C85") (pin "1") (pinfunction "1_1") (pintype "passive"))
      (node (ref "L2") (pin "2") (pinfunction "2_2") (pintype "passive"))
    )
    (net (code "5") (name "DPLL_VDDA_FB") (class "Default")
      (node (ref "C125") (pin "1") (pinfunction "1_1") (pintype "passive"))
      (node (ref "C126") (pin "1") (pinfunction "1_1") (pintype "passive"))
      (node (ref "L13") (pin "2") (pinfunction "2_2") (pintype "passive"))
    )
    (net (code "6") (name "DPLL_VDDA_PDCP_XTAL") (class "Default")
      (node (ref "C100") (pin "1") (pinfunction "1_1") (pintype "passive"))
      (node (ref "C99") (pin "1") (pinfunction "1_1") (pintype "passive"))
      (node (ref "L5") (pin "2") (pinfunction "2_2") (pintype "passive"))
    )
    (net (code "7") (name "DPLL_VDDO_Q0") (class "Default")
      (node (ref "C111") (pin "1") (pinfunction "1_1") (pintype "passive"))
      (node (ref "C112") (pin "1") (pinfunction "1_1") (pintype "passive"))
      (node (ref "L8") (pin "2") (pinfunction "2_2") (pintype "passive"))
    )
    (net (code "8") (name "DPLL_VDDO_Q1") (class "Default")
      (node (ref "C127") (pin "1") (pinfunction "1_1") (pintype "passive"))
      (node (ref "C128") (pin "1") (pinfunction "1_1") (pintype "passive"))
      (node (ref "L12") (pin "2") (pinfunction "2_2") (pintype "passive"))
    )
    (net (code "9") (name "DPLL_VDDO_Q2") (class "Default")
      (node (ref "C139") (pin "1") (pinfunction "1_1") (pintype "passive"))
      (node (ref "C140") (pin "1") (pinfunction "1_1") (pintype "passive"))
      (node (ref "L16") (pin "2") (pinfunction "2_2") (pintype "passive"))
    )
    (net (code "10") (name "DPLL_VDDO_Q3") (class "Default")
      (node (ref "C148") (pin "1") (pinfunction "1_1") (pintype "passive"))
      (node (ref "C149") (pin "1") (pinfunction "1_1") (pintype "passive"))
      (node (ref "L18") (pin "2") (pinfunction "2_2") (pintype "passive"))
    )
    (net (code "11") (name "DPLL_VDDO_Q4") (class "Default")
      (node (ref "C106") (pin "1") (pinfunction "1_1") (pintype "passive"))
      (node (ref "C107") (pin "1") (pinfunction "1_1") (pintype "passive"))
      (node (ref "L7") (pin "2") (pinfunction "2_2") (pintype "passive"))
    )
    (net (code "12") (name "DPLL_VDDO_Q5") (class "Default")
      (node (ref "C118") (pin "1") (pinfunction "1_1") (pintype "passive"))
      (node (ref "C119") (pin "1") (pinfunction "1_1") (pintype "passive"))
      (node (ref "L10") (pin "2") (pinfunction "2_2") (pintype "passive"))
    )
    (net (code "13") (name "DPLL_VDDO_Q6") (class "Default")
      (node (ref "C132") (pin "1") (pinfunction "1_1") (pintype "passive"))
      (node (ref "C133") (pin "1") (pinfunction "1_1") (pintype "passive"))
      (node (ref "L14") (pin "2") (pinfunction "2_2") (pintype "passive"))
    )
    (net (code "14") (name "DPLL_VDDO_Q7") (class "Default")
      (node (ref "C143") (pin "1") (pinfunction "1_1") (pintype "passive"))
      (node (ref "C144") (pin "1") (pinfunction "1_1") (pintype "passive"))
      (node (ref "L17") (pin "2") (pinfunction "2_2") (pintype "passive"))
    )
    (net (code "15") (name "DPLL_VDD_CLKA") (class "Default")
      (node (ref "C134") (pin "1") (pinfunction "1_1") (pintype "passive"))
      (node (ref "C135") (pin "1") (pinfunction "1_1") (pintype "passive"))
      (node (ref "L15") (pin "2") (pinfunction "2_2") (pintype "passive"))
    )
    (net (code "16") (name "DPLL_VDD_CLKB") (class "Default")
      (node (ref "C120") (pin "1") (pinfunction "1_1") (pintype "passive"))
      (node (ref "C121") (pin "1") (pinfunction "1_1") (pintype "passive"))
      (node (ref "L11") (pin "2") (pinfunction "2_2") (pintype "passive"))
    )
    (net (code "17") (name "DPLL_VDD_DCO_Q0123") (class "Default")
      (node (ref "C102") (pin "1") (pinfunction "1_1") (pintype "passive"))
      (node (ref "C103") (pin "1") (pinfunction "1_1") (pintype "passive"))
      (node (ref "L6") (pin "2") (pinfunction "2_2") (pintype "passive"))
    )
    (net (code "18") (name "DPLL_VDD_DCO_Q4567") (class "Default")
      (node (ref "C113") (pin "1") (pinfunction "1_1") (pintype "passive"))
      (node (ref "C114") (pin "1") (pinfunction "1_1") (pintype "passive"))
      (node (ref "L9") (pin "2") (pinfunction "2_2") (pintype "passive"))
    )
    (net (code "19") (name "DPLL_VDD_DIA_A") (class "Default")
      (node (ref "C77") (pin "1") (pinfunction "1_1") (pintype "passive"))
      (node (ref "C78") (pin "1") (pinfunction "1_1") (pintype "passive"))
      (node (ref "L3") (pin "2") (pinfunction "2_2") (pintype "passive"))
    )
    (net (code "20") (name "DPLL_VDD_DIA_B") (class "Default")
      (node (ref "C92") (pin "1") (pinfunction "1_1") (pintype "passive"))
      (node (ref "C93") (pin "1") (pinfunction "1_1") (pintype "passive"))
      (node (ref "L4") (pin "2") (pinfunction "2_2") (pintype "passive"))
    )
    (net (code "21") (name "DPLL_VDD_DIG") (class "Default")
      (node (ref "C79") (pin "1") (pinfunction "1_1") (pintype "passive"))
      (node (ref "C80") (pin "1") (pinfunction "1_1") (pintype "passive"))
      (node (ref "C81") (pin "1") (pinfunction "1_1") (pintype "passive"))
      (node (ref "C82") (pin "1") (pinfunction "1_1") (pintype "passive"))
      (node (ref "R79") (pin "2") (pinfunction "2_2") (pintype "passive"))
    )
    (net (code "22") (name "DPLL_VDD_GPIO") (class "Default")
      (node (ref "C95") (pin "1") (pinfunction "1_1") (pintype "passive"))
      (node (ref "C96") (pin "1") (pinfunction "1_1") (pintype "passive"))
      (node (ref "C97") (pin "1") (pinfunction "1_1") (pintype "passive"))
      (node (ref "C98") (pin "1") (pinfunction "1_1") (pintype "passive"))
      (node (ref "R80") (pin "2") (pinfunction "2_2") (pintype "passive"))
    )
    (net (code "23") (name "DPLL_XO") (class "Default")
      (node (ref "R81") (pin "1") (pinfunction "1_1") (pintype "passive"))
    )
    (net (code "24") (name "GND") (class "Default")
      (node (ref "C100") (pin "2") (pinfunction "2_2") (pintype "passive"))
      (node (ref "C101") (pin "2") (pinfunction "2_2") (pintype "passive"))
      (node (ref "C102") (pin "2") (pinfunction "2_2") (pintype "passive"))
      (node (ref "C103") (pin "2") (pinfunction "2_2") (pintype "passive"))
      (node (ref "C104") (pin "2") (pinfunction "2_2") (pintype "passive"))
      (node (ref "C105") (pin "2") (pinfunction "2_2") (pintype "passive"))
      (node (ref "C106") (pin "2") (pinfunction "2_2") (pintype "passive"))
      (node (ref "C107") (pin "2") (pinfunction "2_2") (pintype "passive"))
      (node (ref "C108") (pin "2") (pinfunction "2_2") (pintype "passive"))
      (node (ref "C109") (pin "2") (pinfunction "2_2") (pintype "passive"))
      (node (ref "C110") (pin "2") (pinfunction "2_2") (pintype "passive"))
      (node (ref "C111") (pin "2") (pinfunction "2_2") (pintype "passive"))
      (node (ref "C112") (pin "2") (pinfunction "2_2") (pintype "passive"))
      (node (ref "C113") (pin "2") (pinfunction "2_2") (pintype "passive"))
      (node (ref "C114") (pin "2") (pinfunction "2_2") (pintype "passive"))
      (node (ref "C115") (pin "2") (pinfunction "2_2") (pintype "passive"))
      (node (ref "C116") (pin "2") (pinfunction "2_2") (pintype "passive"))
      (node (ref "C117") (pin "2") (pinfunction "2_2") (pintype "passive"))
      (node (ref "C118") (pin "2") (pinfunction "2_2") (pintype "passive"))
      (node (ref "C119") (pin "2") (pinfunction "2_2") (pintype "passive"))
      (node (ref "C120") (pin "2") (pinfunction "2_2") (pintype "passive"))
      (node (ref "C121") (pin "2") (pinfunction "2_2") (pintype "passive"))
      (node (ref "C122") (pin "2") (pinfunction "2_2") (pintype "passive"))
      (node (ref "C123") (pin "2") (pinfunction "2_2") (pintype "passive"))
      (node (ref "C124") (pin "2") (pinfunction "2_2") (pintype "passive"))
      (node (ref "C125") (pin "2") (pinfunction "2_2") (pintype "passive"))
      (node (ref "C126") (pin "2") (pinfunction "2_2") (pintype "passive"))
      (node (ref "C127") (pin "2") (pinfunction "2_2") (pintype "passive"))
      (node (ref "C128") (pin "2") (pinfunction "2_2") (pintype "passive"))
      (node (ref "C129") (pin "2") (pinfunction "2_2") (pintype "passive"))
      (node (ref "C130") (pin "2") (pinfunction "2_2") (pintype "passive"))
      (node (ref "C131") (pin "2") (pinfunction "2_2") (pintype "passive"))
      (node (ref "C132") (pin "2") (pinfunction "2_2") (pintype "passive"))
      (node (ref "C133") (pin "2") (pinfunction "2_2") (pintype "passive"))
      (node (ref "C134") (pin "2") (pinfunction "2_2") (pintype "passive"))
      (node (ref "C135") (pin "2") (pinfunction "2_2") (pintype "passive"))
      (node (ref "C136") (pin "2") (pinfunction "2_2") (pintype "passive"))
      (node (ref "C137") (pin "2") (pinfunction "2_2") (pintype "passive"))
      (node (ref "C138") (pin "2") (pinfunction "2_2") (pintype "passive"))
      (node (ref "C139") (pin "2") (pinfunction "2_2") (pintype "passive"))
      (node (ref "C140") (pin "2") (pinfunction "2_2") (pintype "passive"))
      (node (ref "C141") (pin "2") (pinfunction "2_2") (pintype "passive"))
      (node (ref "C142") (pin "2") (pinfunction "2_2") (pintype "passive"))
      (node (ref "C143") (pin "2") (pinfunction "2_2") (pintype "passive"))
      (node (ref "C144") (pin "2") (pinfunction "2_2") (pintype "passive"))
      (node (ref "C145") (pin "1") (pinfunction "1_1") (pintype "passive"))
      (node (ref "C146") (pin "2") (pinfunction "2_2") (pintype "passive"))
      (node (ref "C147") (pin "2") (pinfunction "2_2") (pintype "passive"))
      (node (ref "C148") (pin "2") (pinfunction "2_2") (pintype "passive"))
      (node (ref "C149") (pin "2") (pinfunction "2_2") (pintype "passive"))
      (node (ref "C150") (pin "2") (pinfunction "2_2") (pintype "passive"))
      (node (ref "C151") (pin "1") (pinfunction "1_1") (pintype "passive"))
      (node (ref "C153") (pin "2") (pinfunction "2_2") (pintype "passive"))
      (node (ref "C154") (pin "2") (pinfunction "2_2") (pintype "passive"))
      (node (ref "C155") (pin "2") (pinfunction "2_2") (pintype "passive"))
      (node (ref "C156") (pin "2") (pinfunction "2_2") (pintype "passive"))
      (node (ref "C77") (pin "2") (pinfunction "2_2") (pintype "passive"))
      (node (ref "C78") (pin "2") (pinfunction "2_2") (pintype "passive"))
      (node (ref "C79") (pin "2") (pinfunction "2_2") (pintype "passive"))
      (node (ref "C80") (pin "2") (pinfunction "2_2") (pintype "passive"))
      (node (ref "C81") (pin "2") (pinfunction "2_2") (pintype "passive"))
      (node (ref "C82") (pin "2") (pinfunction "2_2") (pintype "passive"))
      (node (ref "C83") (pin "2") (pinfunction "2_2") (pintype "passive"))
      (node (ref "C84") (pin "2") (pinfunction "2_2") (pintype "passive"))
      (node (ref "C85") (pin "2") (pinfunction "2_2") (pintype "passive"))
      (node (ref "C86") (pin "2") (pinfunction "2_2") (pintype "passive"))
      (node (ref "C87") (pin "2") (pinfunction "2_2") (pintype "passive"))
      (node (ref "C88") (pin "2") (pinfunction "2_2") (pintype "passive"))
      (node (ref "C89") (pin "2") (pinfunction "2_2") (pintype "passive"))
      (node (ref "C90") (pin "2") (pinfunction "2_2") (pintype "passive"))
      (node (ref "C91") (pin "2") (pinfunction "2_2") (pintype "passive"))
      (node (ref "C92") (pin "2") (pinfunction "2_2") (pintype "passive"))
      (node (ref "C93") (pin "2") (pinfunction "2_2") (pintype "passive"))
      (node (ref "C94") (pin "2") (pinfunction "2_2") (pintype "passive"))
      (node (ref "C95") (pin "2") (pinfunction "2_2") (pintype "passive"))
      (node (ref "C96") (pin "2") (pinfunction "2_2") (pintype "passive"))
      (node (ref "C97") (pin "2") (pinfunction "2_2") (pintype "passive"))
      (node (ref "C98") (pin "2") (pinfunction "2_2") (pintype "passive"))
      (node (ref "C99") (pin "2") (pinfunction "2_2") (pintype "passive"))
      (node (ref "R89") (pin "1") (pinfunction "1_1") (pintype "passive"))
      (node (ref "Y2") (pin "5") (pinfunction "GND_5") (pintype "power_in"))
      (node (ref "Y3") (pin "3") (pinfunction "GND_3") (pintype "power_in"))
    )
    (net (code "25") (name "Net-(C152-Pad1)") (class "Default")
      (node (ref "C152") (pin "1") (pinfunction "1_1") (pintype "passive"))
      (node (ref "R87") (pin "1") (pinfunction "1_1") (pintype "passive"))
      (node (ref "R88") (pin "2") (pinfunction "2_2") (pintype "passive"))
      (node (ref "R89") (pin "2") (pinfunction "2_2") (pintype "passive"))
    )
    (net (code "26") (name "Net-(R83-Pad1)") (class "Default")
      (node (ref "R83") (pin "1") (pinfunction "1_1") (pintype "passive"))
      (node (ref "Y2") (pin "7") (pinfunction "NC_7") (pintype "passive"))
    )
    (net (code "27") (name "Net-(R84-Pad1)") (class "Default")
      (node (ref "R84") (pin "1") (pinfunction "1_1") (pintype "passive"))
      (node (ref "Y2") (pin "8") (pinfunction "NC_8") (pintype "passive"))
    )
    (net (code "28") (name "Net-(Y2-CLK)") (class "Default")
      (node (ref "R81") (pin "2") (pinfunction "2_2") (pintype "passive"))
      (node (ref "Y2") (pin "6") (pinfunction "CLK_6") (pintype "output"))
    )
    (net (code "29") (name "Net-(Y2-OE)") (class "Default")
      (node (ref "R82") (pin "2") (pinfunction "2_2") (pintype "passive"))
      (node (ref "Y2") (pin "1") (pinfunction "OE_1") (pintype "input"))
    )
    (net (code "30") (name "Net-(Y2-VDD)") (class "Default")
      (node (ref "C150") (pin "1") (pinfunction "1_1") (pintype "passive"))
      (node (ref "C151") (pin "2") (pinfunction "2_2") (pintype "passive"))
      (node (ref "FB5") (pin "1") (pinfunction "1_1") (pintype "passive"))
      (node (ref "R82") (pin "1") (pinfunction "1_1") (pintype "passive"))
      (node (ref "Y2") (pin "10") (pinfunction "VDD_10") (pintype "power_in"))
    )
    (net (code "31") (name "Net-(Y3-Output)") (class "Default")
      (node (ref "R88") (pin "1") (pinfunction "1_1") (pintype "passive"))
      (node (ref "Y3") (pin "4") (pinfunction "Output_4") (pintype "output"))
    )
    (net (code "32") (name "Net-(Y3-VDD)") (class "Default")
      (node (ref "C155") (pin "1") (pinfunction "1_1") (pintype "passive"))
      (node (ref "C156") (pin "1") (pinfunction "1_1") (pintype "passive"))
      (node (ref "L19") (pin "2") (pinfunction "2_2") (pintype "passive"))
      (node (ref "Y3") (pin "1") (pinfunction "~{Tri-State}_1") (pintype "input"))
      (node (ref "Y3") (pin "6") (pinfunction "VDD_6") (pintype "power_in"))
    )
    (net (code "33") (name "P1V8_DPLL") (class "Default")
      (node (ref "C108") (pin "1") (pinfunction "1_1") (pintype "passive"))
      (node (ref "C115") (pin "1") (pinfunction "1_1") (pintype "passive"))
      (node (ref "C129") (pin "1") (pinfunction "1_1") (pintype "passive"))
      (node (ref "C88") (pin "1") (pinfunction "1_1") (pintype "passive"))
      (node (ref "C89") (pin "1") (pinfunction "1_1") (pintype "passive"))
      (node (ref "C90") (pin "1") (pinfunction "1_1") (pintype "passive"))
      (node (ref "C94") (pin "1") (pinfunction "1_1") (pintype "passive"))
      (node (ref "L13") (pin "1") (pinfunction "1_1") (pintype "passive"))
      (node (ref "L3") (pin "1") (pinfunction "1_1") (pintype "passive"))
      (node (ref "L4") (pin "1") (pinfunction "1_1") (pintype "passive"))
      (node (ref "L6") (pin "1") (pinfunction "1_1") (pintype "passive"))
      (node (ref "L9") (pin "1") (pinfunction "1_1") (pintype "passive"))
      (node (ref "R79") (pin "1") (pinfunction "1_1") (pintype "passive"))
    )
    (net (code "34") (name "P3V3") (class "Default")
      (node (ref "C101") (pin "1") (pinfunction "1_1") (pintype "passive"))
      (node (ref "C104") (pin "1") (pinfunction "1_1") (pintype "passive"))
      (node (ref "C105") (pin "1") (pinfunction "1_1") (pintype "passive"))
      (node (ref "C109") (pin "1") (pinfunction "1_1") (pintype "passive"))
      (node (ref "C110") (pin "1") (pinfunction "1_1") (pintype "passive"))
      (node (ref "C116") (pin "1") (pinfunction "1_1") (pintype "passive"))
      (node (ref "C117") (pin "1") (pinfunction "1_1") (pintype "passive"))
      (node (ref "C122") (pin "1") (pinfunction "1_1") (pintype "passive"))
      (node (ref "C123") (pin "1") (pinfunction "1_1") (pintype "passive"))
      (node (ref "C124") (pin "1") (pinfunction "1_1") (pintype "passive"))
      (node (ref "C130") (pin "1") (pinfunction "1_1") (pintype "passive"))
      (node (ref "C131") (pin "1") (pinfunction "1_1") (pintype "passive"))
      (node (ref "C136") (pin "1") (pinfunction "1_1") (pintype "passive"))
      (node (ref "C137") (pin "1") (pinfunction "1_1") (pintype "passive"))
      (node (ref "C138") (pin "1") (pinfunction "1_1") (pintype "passive"))
      (node (ref "C141") (pin "1") (pinfunction "1_1") (pintype "passive"))
      (node (ref "C142") (pin "1") (pinfunction "1_1") (pintype "passive"))
      (node (ref "C145") (pin "2") (pinfunction "2_2") (pintype "passive"))
      (node (ref "C146") (pin "1") (pinfunction "1_1") (pintype "passive"))
      (node (ref "C147") (pin "1") (pinfunction "1_1") (pintype "passive"))
      (node (ref "C153") (pin "1") (pinfunction "1_1") (pintype "passive"))
      (node (ref "C154") (pin "1") (pinfunction "1_1") (pintype "passive"))
      (node (ref "C86") (pin "1") (pinfunction "1_1") (pintype "passive"))
      (node (ref "C87") (pin "1") (pinfunction "1_1") (pintype "passive"))
      (node (ref "C91") (pin "1") (pinfunction "1_1") (pintype "passive"))
      (node (ref "FB5") (pin "2") (pinfunction "2_2") (pintype "passive"))
      (node (ref "L10") (pin "1") (pinfunction "1_1") (pintype "passive"))
      (node (ref "L11") (pin "1") (pinfunction "1_1") (pintype "passive"))
      (node (ref "L12") (pin "1") (pinfunction "1_1") (pintype "passive"))
      (node (ref "L14") (pin "1") (pinfunction "1_1") (pintype "passive"))
      (node (ref "L15") (pin "1") (pinfunction "1_1") (pintype "passive"))
      (node (ref "L16") (pin "1") (pinfunction "1_1") (pintype "passive"))
      (node (ref "L17") (pin "1") (pinfunction "1_1") (pintype "passive"))
      (node (ref "L18") (pin "1") (pinfunction "1_1") (pintype "passive"))
      (node (ref "L19") (pin "1") (pinfunction "1_1") (pintype "passive"))
      (node (ref "L2") (pin "1") (pinfunction "1_1") (pintype "passive"))
      (node (ref "L5") (pin "1") (pinfunction "1_1") (pintype "passive"))
      (node (ref "L7") (pin "1") (pinfunction "1_1") (pintype "passive"))
      (node (ref "L8") (pin "1") (pinfunction "1_1") (pintype "passive"))
      (node (ref "R80") (pin "1") (pinfunction "1_1") (pintype "passive"))
      (node (ref "R83") (pin "2") (pinfunction "2_2") (pintype "passive"))
      (node (ref "R84") (pin "2") (pinfunction "2_2") (pintype "passive"))
      (node (ref "R87") (pin "2") (pinfunction "2_2") (pintype "passive"))
    )
    (net (code "35") (name "unconnected-(Y2-NC-Pad4)") (class "Default")
      (node (ref "Y2") (pin "4") (pinfunction "NC_4") (pintype "passive"))
    )
    (net (code "36") (name "unconnected-(Y2-NC-Pad9)") (class "Default")
      (node (ref "Y2") (pin "9") (pinfunction "NC_9") (pintype "passive"))
    )
  )
)
